# NSTTL.net
KiCad netlist of a schematic drawn in Altium Designer
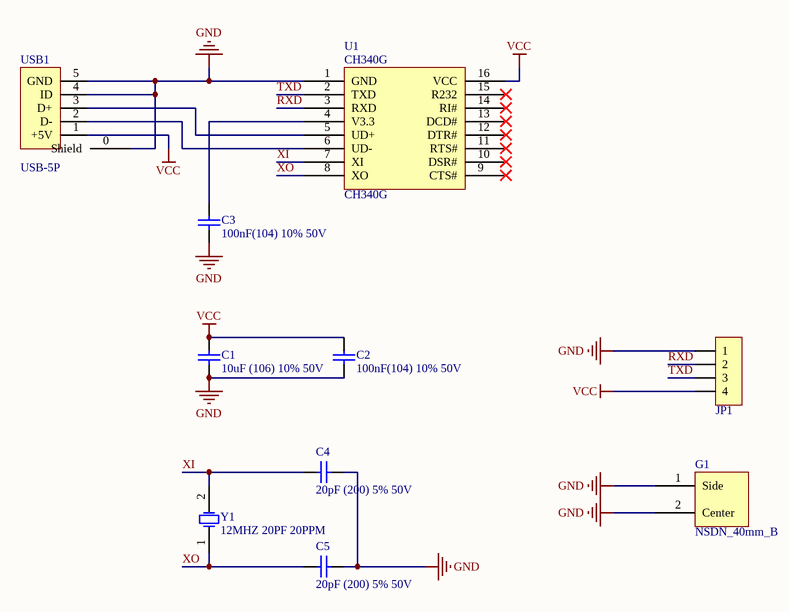
[diagram p0: NSTTL.SchDoc]

(export (version "E")
  (design (tool "Eeschema 10.0.6"))
  (components
    (comp (ref "C1")
      (value "10uF (106) 10% 50V")
      (footprint "1206_C")
      (description "贴片电容")
      (libsource (lib "Miscellaneous Devices LC") (part "1206 10uF (106) 10% 50V"))
    )
    (comp (ref "C2")
      (value "100nF(104) 10% 50V")
      (footprint "0805_C")
      (description "贴片电容")
      (libsource (lib "Miscellaneous Devices LC") (part "0805 100nF(104) 10% 50V"))
    )
    (comp (ref "C3")
      (value "100nF(104) 10% 50V")
      (footprint "0805_C")
      (description "贴片电容")
      (libsource (lib "Miscellaneous Devices LC") (part "0805 100nF(104) 10% 50V"))
    )
    (comp (ref "C4")
      (value "20pF (200) 5% 50V")
      (footprint "0805_C")
      (description "贴片电容")
      (libsource (lib "Miscellaneous Devices LC") (part "0805 20pF (200) 5% 50V"))
    )
    (comp (ref "C5")
      (value "20pF (200) 5% 50V")
      (footprint "0805_C")
      (description "贴片电容")
      (libsource (lib "Miscellaneous Devices LC") (part "0805 20pF (200) 5% 50V"))
    )
    (comp (ref "G1")
      (value "NSDN_40mm_B")
      (footprint "NSDN_40mm_B")
      (libsource (lib "NSDN_40mm") (part "NSDN_40mm_B"))
    )
    (comp (ref "JP1")
      (value "HDR-1X4")
      (footprint "HDR2.54-WS-4P")
      (description "4P接插件")
      (fields (field (name "版权归属") "源创客"))
      (libsource (lib "4.5   - 接插件-脚距2.54") (part "Header 4"))
    )
    (comp (ref "U1")
      (value "CH340G")
      (footprint "SOIC-16_150mil")
      (description "USB")
      (libsource (lib "Miscellaneous Devices LC") (part "CH340G_[C14267]"))
    )
    (comp (ref "USB1")
      (value "USB-5P")
      (footprint "USB-MICRO_D")
      (description "微型USB母座")
      (fields (field (name "版权归属") "源创客"))
      (libsource (lib "4.1   - 接口类") (part "USB-5P"))
    )
    (comp (ref "Y1")
      (value "12MHZ 20PF 20PPM")
      (footprint "SMD-5032_2P")
      (description "贴片晶振")
      (libsource (lib "Miscellaneous Devices LC") (part "SMD-5032_2P 11.0592MHZ 20PF 20PPM"))
    )
  )
  (nets
    (net (code "1") (name "/RXD") (class "Default")
      (node (ref "JP1") (pin "2") (pinfunction "2_2") (pintype "passive"))
      (node (ref "U1") (pin "3") (pinfunction "RXD_3") (pintype "passive"))
    )
    (net (code "2") (name "/TXD") (class "Default")
      (node (ref "JP1") (pin "3") (pinfunction "3_3") (pintype "passive"))
      (node (ref "U1") (pin "2") (pinfunction "TXD_2") (pintype "passive"))
    )
    (net (code "3") (name "/XI") (class "Default")
      (node (ref "C4") (pin "1") (pinfunction "1_1") (pintype "passive"))
      (node (ref "U1") (pin "7") (pinfunction "XI_7") (pintype "passive"))
      (node (ref "Y1") (pin "2") (pinfunction "OSC2_2") (pintype "passive"))
    )
    (net (code "4") (name "/XO") (class "Default")
      (node (ref "C5") (pin "2") (pinfunction "2_2") (pintype "passive"))
      (node (ref "U1") (pin "8") (pinfunction "XO_8") (pintype "passive"))
      (node (ref "Y1") (pin "1") (pinfunction "OSC1_1") (pintype "passive"))
    )
    (net (code "5") (name "GND") (class "Default")
      (node (ref "C1") (pin "2") (pinfunction "2_2") (pintype "passive"))
      (node (ref "C2") (pin "2") (pinfunction "2_2") (pintype "passive"))
      (node (ref "C3") (pin "2") (pinfunction "2_2") (pintype "passive"))
      (node (ref "C4") (pin "2") (pinfunction "2_2") (pintype "passive"))
      (node (ref "C5") (pin "1") (pinfunction "1_1") (pintype "passive"))
      (node (ref "G1") (pin "1") (pinfunction "Side_1") (pintype "passive"))
      (node (ref "G1") (pin "2") (pinfunction "Center_2") (pintype "passive"))
      (node (ref "JP1") (pin "1") (pinfunction "1_1") (pintype "passive"))
      (node (ref "U1") (pin "1") (pinfunction "GND_1") (pintype "passive"))
      (node (ref "USB1") (pin "0") (pinfunction "Shield_0") (pintype "passive"))
      (node (ref "USB1") (pin "4") (pinfunction "ID_4") (pintype "passive"))
      (node (ref "USB1") (pin "5") (pinfunction "GND_5") (pintype "passive"))
    )
    (net (code "6") (name "Net-(U1-UD+)") (class "Default")
      (node (ref "U1") (pin "5") (pinfunction "UD+_5") (pintype "passive"))
      (node (ref "USB1") (pin "3") (pinfunction "D+_3") (pintype "passive"))
    )
    (net (code "7") (name "Net-(U1-UD-)") (class "Default")
      (node (ref "U1") (pin "6") (pinfunction "UD-_6") (pintype "passive"))
      (node (ref "USB1") (pin "2") (pinfunction "D-_2") (pintype "passive"))
    )
    (net (code "8") (name "Net-(U1-V3.3)") (class "Default")
      (node (ref "C3") (pin "1") (pinfunction "1_1") (pintype "passive"))
      (node (ref "U1") (pin "4") (pinfunction "V3.3_4") (pintype "passive"))
    )
    (net (code "9") (name "VCC") (class "Default")
      (node (ref "C1") (pin "1") (pinfunction "1_1") (pintype "passive"))
      (node (ref "C2") (pin "1") (pinfunction "1_1") (pintype "passive"))
      (node (ref "JP1") (pin "4") (pinfunction "4_4") (pintype "passive"))
      (node (ref "U1") (pin "16") (pinfunction "VCC_16") (pintype "passive"))
      (node (ref "USB1") (pin "1") (pinfunction "+5V_1") (pintype "passive"))
    )
    (net (code "10") (name "unconnected-(U1-CTS#-Pad9)") (class "Default")
      (node (ref "U1") (pin "9") (pinfunction "CTS#_9") (pintype "passive+no_connect"))
    )
    (net (code "11") (name "unconnected-(U1-DCD#-Pad13)") (class "Default")
      (node (ref "U1") (pin "13") (pinfunction "DCD#_13") (pintype "passive+no_connect"))
    )
    (net (code "12") (name "unconnected-(U1-DSR#-Pad10)") (class "Default")
      (node (ref "U1") (pin "10") (pinfunction "DSR#_10") (pintype "passive+no_connect"))
    )
    (net (code "13") (name "unconnected-(U1-DTR#-Pad12)") (class "Default")
      (node (ref "U1") (pin "12") (pinfunction "DTR#_12") (pintype "passive+no_connect"))
    )
    (net (code "14") (name "unconnected-(U1-R232-Pad15)") (class "Default")
      (node (ref "U1") (pin "15") (pinfunction "R232_15") (pintype "passive+no_connect"))
    )
    (net (code "15") (name "unconnected-(U1-RI#-Pad14)") (class "Default")
      (node (ref "U1") (pin "14") (pinfunction "RI#_14") (pintype "passive+no_connect"))
    )
    (net (code "16") (name "unconnected-(U1-RTS#-Pad11)") (class "Default")
      (node (ref "U1") (pin "11") (pinfunction "RTS#_11") (pintype "passive+no_connect"))
    )
  )
)
